# Plant_Waterer.net
KiCad netlist of a schematic drawn in EAGLE
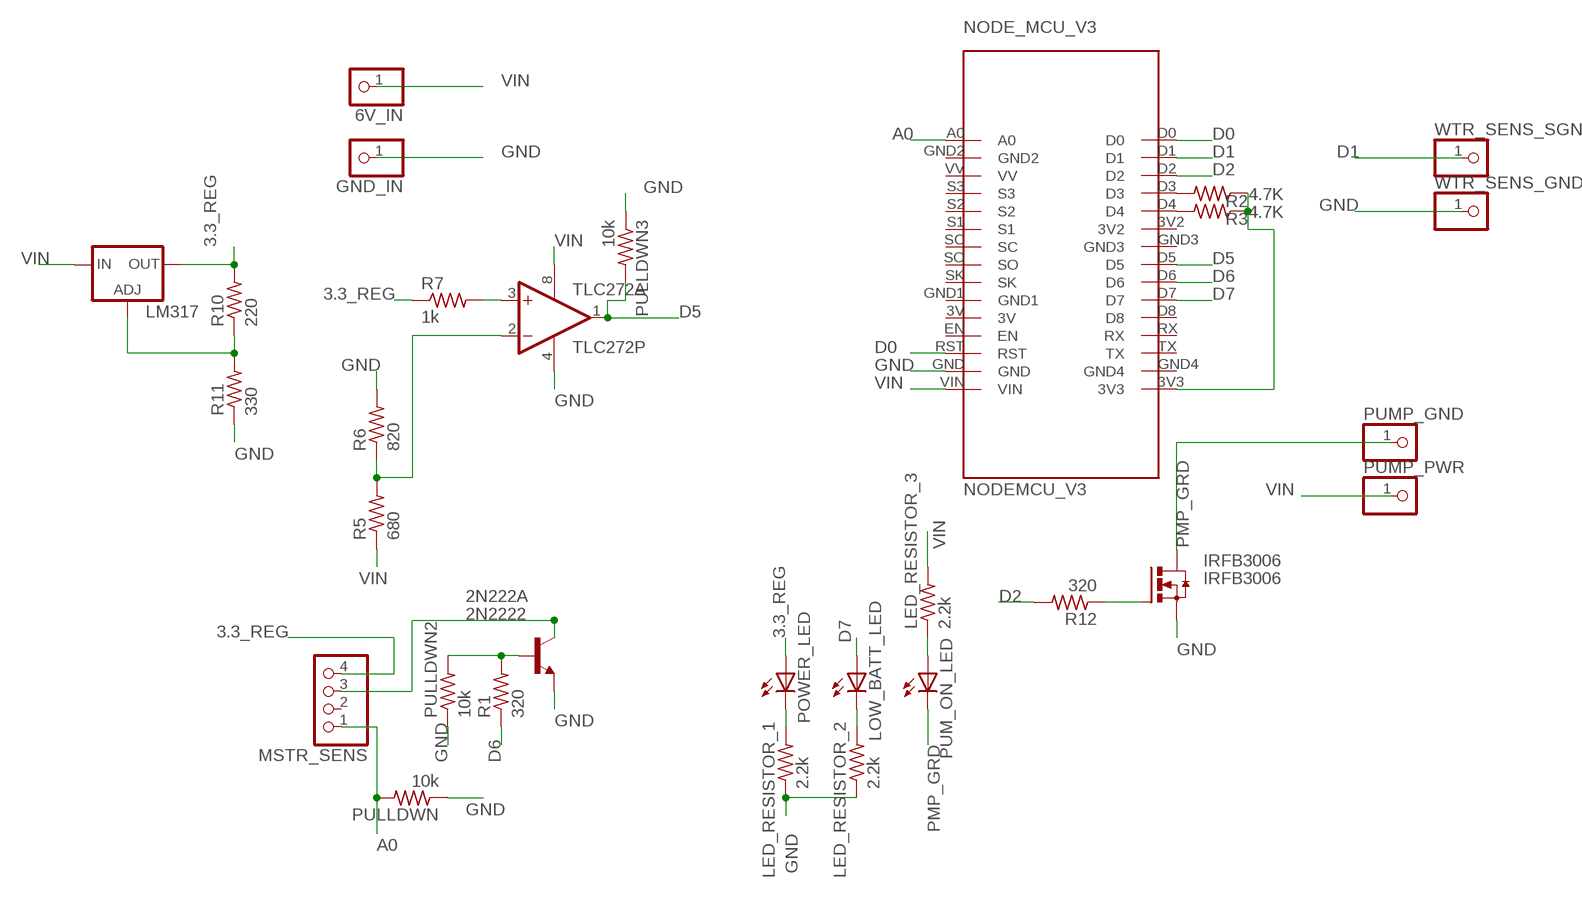
[diagram p0: schematic, sheet 1]

(export (version "E")
  (design (tool "Eeschema 10.0.6"))
  (components
    (comp (ref "2N222A")
      (value "2N2222")
      (footprint "eagle-import:TO92-EBC-OVAL")
      (libsource (lib "eagle-import") (part "2N2222"))
    )
    (comp (ref "6V_IN")
      (value "PINHD-1X1")
      (footprint "eagle-import:1X01")
      (libsource (lib "eagle-import") (part "PINHD-1X1"))
    )
    (comp (ref "GND_IN")
      (value "PINHD-1X1")
      (footprint "eagle-import:1X01")
      (libsource (lib "eagle-import") (part "PINHD-1X1"))
    )
    (comp (ref "IRFB3006")
      (value "IRFB3006")
      (footprint "eagle-import:TO262-V")
      (libsource (lib "eagle-import") (part "IRF3704L-V"))
    )
    (comp (ref "LED_RESISTOR_1")
      (value "2.2k")
      (footprint "eagle-import:0207_10")
      (libsource (lib "eagle-import") (part "R-US_0207/10"))
    )
    (comp (ref "LED_RESISTOR_2")
      (value "2.2k")
      (footprint "eagle-import:0207_10")
      (libsource (lib "eagle-import") (part "R-US_0207/10"))
    )
    (comp (ref "LED_RESISTOR_3")
      (value "2.2k")
      (footprint "eagle-import:0207_10")
      (libsource (lib "eagle-import") (part "R-US_0207/10"))
    )
    (comp (ref "LM317")
      (value "LM317TS")
      (footprint "eagle-import:317TS")
      (libsource (lib "eagle-import") (part "LM317TS"))
    )
    (comp (ref "LOW_BATT_LED")
      (value "LED5MM")
      (footprint "eagle-import:LED5MM")
      (libsource (lib "eagle-import") (part "LED5MM"))
    )
    (comp (ref "MSTR_SENS")
      (value "PINHD-1X4")
      (footprint "eagle-import:1X04")
      (libsource (lib "eagle-import") (part "PINHD-1X4"))
    )
    (comp (ref "NODE_MCU")
      (value "NODEMCU_V3")
      (footprint "eagle-import:NODEMCU_V3")
      (libsource (lib "eagle-import") (part "NODEMCU_V3"))
    )
    (comp (ref "POWER_LED")
      (value "LED5MM")
      (footprint "eagle-import:LED5MM")
      (libsource (lib "eagle-import") (part "LED5MM"))
    )
    (comp (ref "PULLDWN")
      (value "10k")
      (footprint "eagle-import:0207_10")
      (libsource (lib "eagle-import") (part "R-US_0207/10"))
    )
    (comp (ref "PULLDWN2")
      (value "10k")
      (footprint "eagle-import:0207_10")
      (libsource (lib "eagle-import") (part "R-US_0207/10"))
    )
    (comp (ref "PULLDWN3")
      (value "10k")
      (footprint "eagle-import:0207_10")
      (libsource (lib "eagle-import") (part "R-US_0207/10"))
    )
    (comp (ref "PUMP_GND")
      (value "PINHD-1X1")
      (footprint "eagle-import:1X01")
      (libsource (lib "eagle-import") (part "PINHD-1X1"))
    )
    (comp (ref "PUMP_PWR")
      (value "PINHD-1X1")
      (footprint "eagle-import:1X01")
      (libsource (lib "eagle-import") (part "PINHD-1X1"))
    )
    (comp (ref "PUM_ON_LED")
      (value "LED5MM")
      (footprint "eagle-import:LED5MM")
      (libsource (lib "eagle-import") (part "LED5MM"))
    )
    (comp (ref "R1")
      (value "320")
      (footprint "eagle-import:0207_10")
      (libsource (lib "eagle-import") (part "R-US_0207/10"))
    )
    (comp (ref "R2")
      (value "4.7K")
      (footprint "eagle-import:0207_10")
      (libsource (lib "eagle-import") (part "R-US_0207/10"))
    )
    (comp (ref "R3")
      (value "4.7K")
      (footprint "eagle-import:0207_10")
      (libsource (lib "eagle-import") (part "R-US_0207/10"))
    )
    (comp (ref "R5")
      (value "680")
      (footprint "eagle-import:0207_10")
      (libsource (lib "eagle-import") (part "R-US_0207/10"))
    )
    (comp (ref "R6")
      (value "820")
      (footprint "eagle-import:0207_10")
      (libsource (lib "eagle-import") (part "R-US_0207/10"))
    )
    (comp (ref "R7")
      (value "1k")
      (footprint "eagle-import:0207_10")
      (libsource (lib "eagle-import") (part "R-US_0207/10"))
    )
    (comp (ref "R10")
      (value "220")
      (footprint "eagle-import:0207_10")
      (libsource (lib "eagle-import") (part "R-US_0207/10"))
    )
    (comp (ref "R11")
      (value "330")
      (footprint "eagle-import:0207_10")
      (libsource (lib "eagle-import") (part "R-US_0207/10"))
    )
    (comp (ref "R12")
      (value "320")
      (footprint "eagle-import:0207_10")
      (libsource (lib "eagle-import") (part "R-US_0207/10"))
    )
    (comp (ref "TLC272")
      (value "TLC272P")
      (footprint "eagle-import:DIL08")
      (libsource (lib "eagle-import") (part "TLC272P"))
    )
    (comp (ref "WTR_SENS_GND")
      (value "PINHD-1X1")
      (footprint "eagle-import:1X01")
      (libsource (lib "eagle-import") (part "PINHD-1X1"))
    )
    (comp (ref "WTR_SENS_SGNL")
      (value "PINHD-1X1")
      (footprint "eagle-import:1X01")
      (libsource (lib "eagle-import") (part "PINHD-1X1"))
    )
  )
  (nets
    (net (code "1") (name "/3.3_REG") (class "Default")
      (node (ref "LM317") (pin "2") (pinfunction "OUT_2") (pintype "passive"))
      (node (ref "MSTR_SENS") (pin "4") (pinfunction "4_4") (pintype "passive"))
      (node (ref "POWER_LED") (pin "A") (pinfunction "A_A") (pintype "passive"))
      (node (ref "R10") (pin "2") (pinfunction "2_2") (pintype "passive"))
      (node (ref "R7") (pin "1") (pinfunction "1_1") (pintype "passive"))
    )
    (net (code "2") (name "/A0") (class "Default")
      (node (ref "MSTR_SENS") (pin "1") (pinfunction "1_1") (pintype "passive"))
      (node (ref "NODE_MCU") (pin "A0") (pinfunction "A0_A0") (pintype "bidirectional"))
      (node (ref "PULLDWN") (pin "2") (pinfunction "2_2") (pintype "passive"))
    )
    (net (code "3") (name "/D0") (class "Default")
      (node (ref "NODE_MCU") (pin "D0") (pinfunction "D0_D0") (pintype "bidirectional"))
      (node (ref "NODE_MCU") (pin "RST") (pinfunction "RST_RST") (pintype "bidirectional"))
    )
    (net (code "4") (name "/D1") (class "Default")
      (node (ref "NODE_MCU") (pin "D1") (pinfunction "D1_D1") (pintype "bidirectional"))
      (node (ref "WTR_SENS_SGNL") (pin "1") (pinfunction "1_1") (pintype "passive"))
    )
    (net (code "5") (name "/D2") (class "Default")
      (node (ref "NODE_MCU") (pin "D2") (pinfunction "D2_D2") (pintype "bidirectional"))
      (node (ref "R12") (pin "2") (pinfunction "2_2") (pintype "passive"))
    )
    (net (code "6") (name "/D5") (class "Default")
      (node (ref "NODE_MCU") (pin "D5") (pinfunction "D5_D5") (pintype "bidirectional"))
      (node (ref "PULLDWN3") (pin "2") (pinfunction "2_2") (pintype "passive"))
      (node (ref "TLC272") (pin "1") (pinfunction "OUT_1") (pintype "output"))
    )
    (net (code "7") (name "/D6") (class "Default")
      (node (ref "NODE_MCU") (pin "D6") (pinfunction "D6_D6") (pintype "bidirectional"))
      (node (ref "R1") (pin "1") (pinfunction "1_1") (pintype "passive"))
    )
    (net (code "8") (name "/D7") (class "Default")
      (node (ref "LOW_BATT_LED") (pin "A") (pinfunction "A_A") (pintype "passive"))
      (node (ref "NODE_MCU") (pin "D7") (pinfunction "D7_D7") (pintype "bidirectional"))
    )
    (net (code "9") (name "/GND") (class "Default")
      (node (ref "2N222A") (pin "E") (pinfunction "E_E") (pintype "passive"))
      (node (ref "GND_IN") (pin "1") (pinfunction "1_1") (pintype "passive"))
      (node (ref "IRFB3006") (pin "3") (pinfunction "S_3") (pintype "passive"))
      (node (ref "LED_RESISTOR_1") (pin "1") (pinfunction "1_1") (pintype "passive"))
      (node (ref "LED_RESISTOR_2") (pin "1") (pinfunction "1_1") (pintype "passive"))
      (node (ref "NODE_MCU") (pin "GND") (pinfunction "GND_GND") (pintype "bidirectional"))
      (node (ref "PULLDWN") (pin "1") (pinfunction "1_1") (pintype "passive"))
      (node (ref "PULLDWN2") (pin "1") (pinfunction "1_1") (pintype "passive"))
      (node (ref "PULLDWN3") (pin "1") (pinfunction "1_1") (pintype "passive"))
      (node (ref "R11") (pin "1") (pinfunction "1_1") (pintype "passive"))
      (node (ref "R6") (pin "2") (pinfunction "2_2") (pintype "passive"))
      (node (ref "TLC272") (pin "4") (pinfunction "V-_4") (pintype "power_in"))
      (node (ref "WTR_SENS_GND") (pin "1") (pinfunction "1_1") (pintype "passive"))
    )
    (net (code "10") (name "/PMP_GRD") (class "Default")
      (node (ref "IRFB3006") (pin "2") (pinfunction "D_2") (pintype "passive"))
      (node (ref "PUMP_GND") (pin "1") (pinfunction "1_1") (pintype "passive"))
      (node (ref "PUM_ON_LED") (pin "K") (pinfunction "C_K") (pintype "passive"))
    )
    (net (code "11") (name "/VIN") (class "Default")
      (node (ref "6V_IN") (pin "1") (pinfunction "1_1") (pintype "passive"))
      (node (ref "LED_RESISTOR_3") (pin "2") (pinfunction "2_2") (pintype "passive"))
      (node (ref "LM317") (pin "3") (pinfunction "IN_3") (pintype "input"))
      (node (ref "NODE_MCU") (pin "VIN") (pinfunction "VIN_VIN") (pintype "bidirectional"))
      (node (ref "PUMP_PWR") (pin "1") (pinfunction "1_1") (pintype "passive"))
      (node (ref "R5") (pin "1") (pinfunction "1_1") (pintype "passive"))
      (node (ref "TLC272") (pin "8") (pinfunction "V+_8") (pintype "power_in"))
    )
    (net (code "12") (name "Net-(2N222A-PadB)") (class "Default")
      (node (ref "2N222A") (pin "B") (pinfunction "B_B") (pintype "passive"))
      (node (ref "PULLDWN2") (pin "2") (pinfunction "2_2") (pintype "passive"))
      (node (ref "R1") (pin "2") (pinfunction "2_2") (pintype "passive"))
    )
    (net (code "13") (name "Net-(2N222A-PadC)") (class "Default")
      (node (ref "2N222A") (pin "C") (pinfunction "C_C") (pintype "passive"))
      (node (ref "MSTR_SENS") (pin "3") (pinfunction "3_3") (pintype "passive"))
    )
    (net (code "14") (name "Net-(IRFB3006-G)") (class "Default")
      (node (ref "IRFB3006") (pin "1") (pinfunction "G_1") (pintype "passive"))
      (node (ref "R12") (pin "1") (pinfunction "1_1") (pintype "passive"))
    )
    (net (code "15") (name "Net-(LED_RESISTOR_3-Pad1)") (class "Default")
      (node (ref "LED_RESISTOR_3") (pin "1") (pinfunction "1_1") (pintype "passive"))
      (node (ref "PUM_ON_LED") (pin "A") (pinfunction "A_A") (pintype "passive"))
    )
    (net (code "16") (name "Net-(LM317-ADJ)") (class "Default")
      (node (ref "LM317") (pin "1") (pinfunction "ADJ_1") (pintype "input"))
      (node (ref "R10") (pin "1") (pinfunction "1_1") (pintype "passive"))
      (node (ref "R11") (pin "2") (pinfunction "2_2") (pintype "passive"))
    )
    (net (code "17") (name "Net-(LOW_BATT_LED-C)") (class "Default")
      (node (ref "LED_RESISTOR_2") (pin "2") (pinfunction "2_2") (pintype "passive"))
      (node (ref "LOW_BATT_LED") (pin "K") (pinfunction "C_K") (pintype "passive"))
    )
    (net (code "18") (name "Net-(NODE_MCU-Pad3V3)") (class "Default")
      (node (ref "NODE_MCU") (pin "3V3") (pinfunction "3V3_3V3") (pintype "bidirectional"))
      (node (ref "R2") (pin "1") (pinfunction "1_1") (pintype "passive"))
      (node (ref "R3") (pin "1") (pinfunction "1_1") (pintype "passive"))
    )
    (net (code "19") (name "Net-(NODE_MCU-PadD3)") (class "Default")
      (node (ref "NODE_MCU") (pin "D3") (pinfunction "D3_D3") (pintype "bidirectional"))
      (node (ref "R2") (pin "2") (pinfunction "2_2") (pintype "passive"))
    )
    (net (code "20") (name "Net-(NODE_MCU-PadD4)") (class "Default")
      (node (ref "NODE_MCU") (pin "D4") (pinfunction "D4_D4") (pintype "bidirectional"))
      (node (ref "R3") (pin "2") (pinfunction "2_2") (pintype "passive"))
    )
    (net (code "21") (name "Net-(POWER_LED-C)") (class "Default")
      (node (ref "LED_RESISTOR_1") (pin "2") (pinfunction "2_2") (pintype "passive"))
      (node (ref "POWER_LED") (pin "K") (pinfunction "C_K") (pintype "passive"))
    )
    (net (code "22") (name "Net-(TLC272A-+IN)") (class "Default")
      (node (ref "R7") (pin "2") (pinfunction "2_2") (pintype "passive"))
      (node (ref "TLC272") (pin "3") (pinfunction "+IN_3") (pintype "input"))
    )
    (net (code "23") (name "Net-(TLC272A--IN)") (class "Default")
      (node (ref "R5") (pin "2") (pinfunction "2_2") (pintype "passive"))
      (node (ref "R6") (pin "1") (pinfunction "1_1") (pintype "passive"))
      (node (ref "TLC272") (pin "2") (pinfunction "-IN_2") (pintype "input"))
    )
    (net (code "24") (name "unconnected-(MSTR_SENS-Pad2)") (class "Default")
      (node (ref "MSTR_SENS") (pin "2") (pinfunction "2_2") (pintype "passive"))
    )
    (net (code "25") (name "unconnected-(NODE_MCU-Pad3V)") (class "Default")
      (node (ref "NODE_MCU") (pin "3V") (pinfunction "3V_3V") (pintype "bidirectional"))
    )
    (net (code "26") (name "unconnected-(NODE_MCU-Pad3V2)") (class "Default")
      (node (ref "NODE_MCU") (pin "3V2") (pinfunction "3V2_3V2") (pintype "bidirectional"))
    )
    (net (code "27") (name "unconnected-(NODE_MCU-PadD8)") (class "Default")
      (node (ref "NODE_MCU") (pin "D8") (pinfunction "D8_D8") (pintype "bidirectional"))
    )
    (net (code "28") (name "unconnected-(NODE_MCU-PadEN)") (class "Default")
      (node (ref "NODE_MCU") (pin "EN") (pinfunction "EN_EN") (pintype "bidirectional"))
    )
    (net (code "29") (name "unconnected-(NODE_MCU-PadGND1)") (class "Default")
      (node (ref "NODE_MCU") (pin "GND1") (pinfunction "GND1_GND1") (pintype "bidirectional"))
    )
    (net (code "30") (name "unconnected-(NODE_MCU-PadGND2)") (class "Default")
      (node (ref "NODE_MCU") (pin "GND2") (pinfunction "GND2_GND2") (pintype "bidirectional"))
    )
    (net (code "31") (name "unconnected-(NODE_MCU-PadGND3)") (class "Default")
      (node (ref "NODE_MCU") (pin "GND3") (pinfunction "GND3_GND3") (pintype "bidirectional"))
    )
    (net (code "32") (name "unconnected-(NODE_MCU-PadGND4)") (class "Default")
      (node (ref "NODE_MCU") (pin "GND4") (pinfunction "GND4_GND4") (pintype "bidirectional"))
    )
    (net (code "33") (name "unconnected-(NODE_MCU-PadRX)") (class "Default")
      (node (ref "NODE_MCU") (pin "RX") (pinfunction "RX_RX") (pintype "bidirectional"))
    )
    (net (code "34") (name "unconnected-(NODE_MCU-PadS1)") (class "Default")
      (node (ref "NODE_MCU") (pin "S1") (pinfunction "S1_S1") (pintype "bidirectional"))
    )
    (net (code "35") (name "unconnected-(NODE_MCU-PadS2)") (class "Default")
      (node (ref "NODE_MCU") (pin "S2") (pinfunction "S2_S2") (pintype "bidirectional"))
    )
    (net (code "36") (name "unconnected-(NODE_MCU-PadS3)") (class "Default")
      (node (ref "NODE_MCU") (pin "S3") (pinfunction "S3_S3") (pintype "bidirectional"))
    )
    (net (code "37") (name "unconnected-(NODE_MCU-PadSC)") (class "Default")
      (node (ref "NODE_MCU") (pin "SC") (pinfunction "SC_SC") (pintype "bidirectional"))
    )
    (net (code "38") (name "unconnected-(NODE_MCU-PadSK)") (class "Default")
      (node (ref "NODE_MCU") (pin "SK") (pinfunction "SK_SK") (pintype "bidirectional"))
    )
    (net (code "39") (name "unconnected-(NODE_MCU-PadSO)") (class "Default")
      (node (ref "NODE_MCU") (pin "SO") (pinfunction "SO_SO") (pintype "bidirectional"))
    )
    (net (code "40") (name "unconnected-(NODE_MCU-PadTX)") (class "Default")
      (node (ref "NODE_MCU") (pin "TX") (pinfunction "TX_TX") (pintype "bidirectional"))
    )
    (net (code "41") (name "unconnected-(NODE_MCU-PadVV)") (class "Default")
      (node (ref "NODE_MCU") (pin "VV") (pinfunction "VV_VV") (pintype "bidirectional"))
    )
  )
)
